# Zynthian_MCP23017.net
KiCad netlist of a schematic drawn in EAGLE
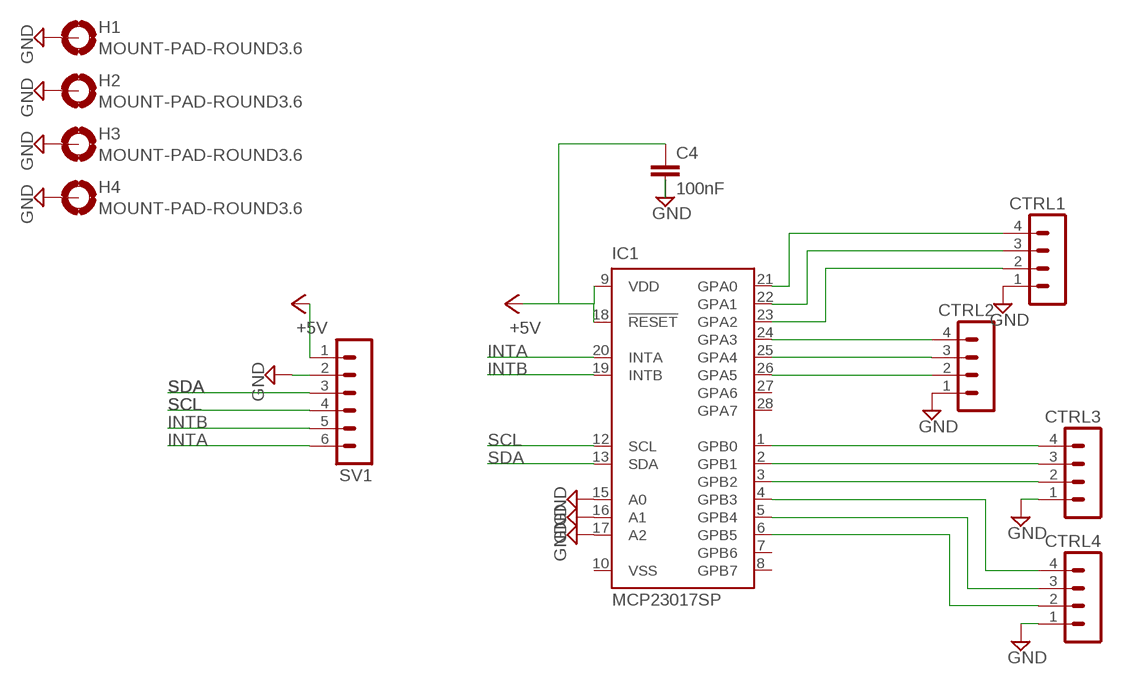
[diagram p0: schematic, sheet 1]

(export (version "E")
  (design (tool "Eeschema 10.0.6"))
  (components
    (comp (ref "C4")
      (value "100nF")
      (footprint "eagle-import:072X025")
      (libsource (lib "eagle-import") (part "072X0252"))
    )
    (comp (ref "CTRL1")
      (value "MA04-1")
      (footprint "eagle-import:MA04-1")
      (libsource (lib "eagle-import") (part "MA04-1"))
    )
    (comp (ref "CTRL2")
      (value "MA04-1")
      (footprint "eagle-import:MA04-1")
      (libsource (lib "eagle-import") (part "MA04-1"))
    )
    (comp (ref "CTRL3")
      (value "MA04-1")
      (footprint "eagle-import:MA04-1")
      (libsource (lib "eagle-import") (part "MA04-1"))
    )
    (comp (ref "CTRL4")
      (value "MA04-1")
      (footprint "eagle-import:MA04-1")
      (libsource (lib "eagle-import") (part "MA04-1"))
    )
    (comp (ref "H1")
      (value "MOUNT-PAD-ROUND3.6")
      (footprint "eagle-import:3,6-PAD")
      (libsource (lib "eagle-import") (part "MOUNT-PAD-ROUND3.6"))
    )
    (comp (ref "H2")
      (value "MOUNT-PAD-ROUND3.6")
      (footprint "eagle-import:3,6-PAD")
      (libsource (lib "eagle-import") (part "MOUNT-PAD-ROUND3.6"))
    )
    (comp (ref "H3")
      (value "MOUNT-PAD-ROUND3.6")
      (footprint "eagle-import:3,6-PAD")
      (libsource (lib "eagle-import") (part "MOUNT-PAD-ROUND3.6"))
    )
    (comp (ref "H4")
      (value "MOUNT-PAD-ROUND3.6")
      (footprint "eagle-import:3,6-PAD")
      (libsource (lib "eagle-import") (part "MOUNT-PAD-ROUND3.6"))
    )
    (comp (ref "IC1")
      (value "MCP23017SP")
      (footprint "eagle-import:DIL28-3")
      (libsource (lib "eagle-import") (part "MCP23017SP"))
    )
    (comp (ref "SV1")
      (value "MA06-1")
      (footprint "eagle-import:MA06-1")
      (libsource (lib "eagle-import") (part "MA06-1"))
    )
  )
  (nets
    (net (code "1") (name "+5V") (class "Default")
      (node (ref "C4") (pin "1") (pinfunction "1_1") (pintype "passive"))
      (node (ref "IC1") (pin "18") (pinfunction "~{RESET}_18") (pintype "input"))
      (node (ref "IC1") (pin "9") (pinfunction "VDD_9") (pintype "power_in"))
      (node (ref "SV1") (pin "1") (pinfunction "1_1") (pintype "passive"))
    )
    (net (code "2") (name "/INTA") (class "Default")
      (node (ref "IC1") (pin "20") (pinfunction "INTA_20") (pintype "output"))
      (node (ref "SV1") (pin "6") (pinfunction "6_6") (pintype "passive"))
    )
    (net (code "3") (name "/INTB") (class "Default")
      (node (ref "IC1") (pin "19") (pinfunction "INTB_19") (pintype "output"))
      (node (ref "SV1") (pin "5") (pinfunction "5_5") (pintype "passive"))
    )
    (net (code "4") (name "/SCL") (class "Default")
      (node (ref "IC1") (pin "12") (pinfunction "SCL_12") (pintype "input"))
      (node (ref "SV1") (pin "4") (pinfunction "4_4") (pintype "passive"))
    )
    (net (code "5") (name "/SDA") (class "Default")
      (node (ref "IC1") (pin "13") (pinfunction "SDA_13") (pintype "bidirectional"))
      (node (ref "SV1") (pin "3") (pinfunction "3_3") (pintype "passive"))
    )
    (net (code "6") (name "/VSS") (class "Default")
      (node (ref "IC1") (pin "10") (pinfunction "VSS_10") (pintype "power_in"))
    )
    (net (code "7") (name "GND") (class "Default")
      (node (ref "C4") (pin "2") (pinfunction "2_2") (pintype "passive"))
      (node (ref "CTRL1") (pin "1") (pinfunction "1_1") (pintype "passive"))
      (node (ref "CTRL2") (pin "1") (pinfunction "1_1") (pintype "passive"))
      (node (ref "CTRL3") (pin "1") (pinfunction "1_1") (pintype "passive"))
      (node (ref "CTRL4") (pin "1") (pinfunction "1_1") (pintype "passive"))
      (node (ref "H1") (pin "B3,6") (pinfunction "MOUNT_B3,6") (pintype "passive"))
      (node (ref "H2") (pin "B3,6") (pinfunction "MOUNT_B3,6") (pintype "passive"))
      (node (ref "H3") (pin "B3,6") (pinfunction "MOUNT_B3,6") (pintype "passive"))
      (node (ref "H4") (pin "B3,6") (pinfunction "MOUNT_B3,6") (pintype "passive"))
      (node (ref "IC1") (pin "15") (pinfunction "A0_15") (pintype "input"))
      (node (ref "IC1") (pin "16") (pinfunction "A1_16") (pintype "input"))
      (node (ref "IC1") (pin "17") (pinfunction "A2_17") (pintype "input"))
      (node (ref "SV1") (pin "2") (pinfunction "2_2") (pintype "passive"))
    )
    (net (code "8") (name "Net-(IC1-GPA0)") (class "Default")
      (node (ref "CTRL1") (pin "4") (pinfunction "4_4") (pintype "passive"))
      (node (ref "IC1") (pin "21") (pinfunction "GPA0_21") (pintype "bidirectional"))
    )
    (net (code "9") (name "Net-(IC1-GPA1)") (class "Default")
      (node (ref "CTRL1") (pin "3") (pinfunction "3_3") (pintype "passive"))
      (node (ref "IC1") (pin "22") (pinfunction "GPA1_22") (pintype "bidirectional"))
    )
    (net (code "10") (name "Net-(IC1-GPA2)") (class "Default")
      (node (ref "CTRL1") (pin "2") (pinfunction "2_2") (pintype "passive"))
      (node (ref "IC1") (pin "23") (pinfunction "GPA2_23") (pintype "bidirectional"))
    )
    (net (code "11") (name "Net-(IC1-GPA3)") (class "Default")
      (node (ref "CTRL2") (pin "4") (pinfunction "4_4") (pintype "passive"))
      (node (ref "IC1") (pin "24") (pinfunction "GPA3_24") (pintype "bidirectional"))
    )
    (net (code "12") (name "Net-(IC1-GPA4)") (class "Default")
      (node (ref "CTRL2") (pin "3") (pinfunction "3_3") (pintype "passive"))
      (node (ref "IC1") (pin "25") (pinfunction "GPA4_25") (pintype "bidirectional"))
    )
    (net (code "13") (name "Net-(IC1-GPA5)") (class "Default")
      (node (ref "CTRL2") (pin "2") (pinfunction "2_2") (pintype "passive"))
      (node (ref "IC1") (pin "26") (pinfunction "GPA5_26") (pintype "bidirectional"))
    )
    (net (code "14") (name "Net-(IC1-GPB0)") (class "Default")
      (node (ref "CTRL3") (pin "4") (pinfunction "4_4") (pintype "passive"))
      (node (ref "IC1") (pin "1") (pinfunction "GPB0_1") (pintype "bidirectional"))
    )
    (net (code "15") (name "Net-(IC1-GPB1)") (class "Default")
      (node (ref "CTRL3") (pin "3") (pinfunction "3_3") (pintype "passive"))
      (node (ref "IC1") (pin "2") (pinfunction "GPB1_2") (pintype "bidirectional"))
    )
    (net (code "16") (name "Net-(IC1-GPB2)") (class "Default")
      (node (ref "CTRL3") (pin "2") (pinfunction "2_2") (pintype "passive"))
      (node (ref "IC1") (pin "3") (pinfunction "GPB2_3") (pintype "bidirectional"))
    )
    (net (code "17") (name "Net-(IC1-GPB3)") (class "Default")
      (node (ref "CTRL4") (pin "4") (pinfunction "4_4") (pintype "passive"))
      (node (ref "IC1") (pin "4") (pinfunction "GPB3_4") (pintype "bidirectional"))
    )
    (net (code "18") (name "Net-(IC1-GPB4)") (class "Default")
      (node (ref "CTRL4") (pin "3") (pinfunction "3_3") (pintype "passive"))
      (node (ref "IC1") (pin "5") (pinfunction "GPB4_5") (pintype "bidirectional"))
    )
    (net (code "19") (name "Net-(IC1-GPB5)") (class "Default")
      (node (ref "CTRL4") (pin "2") (pinfunction "2_2") (pintype "passive"))
      (node (ref "IC1") (pin "6") (pinfunction "GPB5_6") (pintype "bidirectional"))
    )
    (net (code "20") (name "unconnected-(IC1-GPA6-Pad27)") (class "Default")
      (node (ref "IC1") (pin "27") (pinfunction "GPA6_27") (pintype "bidirectional"))
    )
    (net (code "21") (name "unconnected-(IC1-GPA7-Pad28)") (class "Default")
      (node (ref "IC1") (pin "28") (pinfunction "GPA7_28") (pintype "bidirectional"))
    )
    (net (code "22") (name "unconnected-(IC1-GPB6-Pad7)") (class "Default")
      (node (ref "IC1") (pin "7") (pinfunction "GPB6_7") (pintype "bidirectional"))
    )
    (net (code "23") (name "unconnected-(IC1-GPB7-Pad8)") (class "Default")
      (node (ref "IC1") (pin "8") (pinfunction "GPB7_8") (pintype "bidirectional"))
    )
  )
)
